# DataVideoPort.net
KiCad netlist of a schematic drawn in Altium Designer
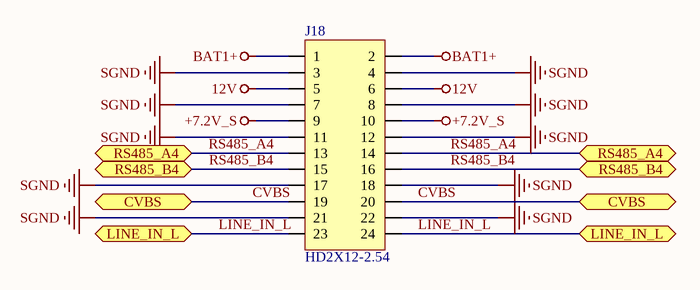
[diagram p0: DataVideoPort.SchDoc]

(export (version "E")
  (design (tool "Eeschema 10.0.6"))
  (components
    (comp (ref "J18")
      (value "HD2X12-2.54")
      (footprint "HD2X12-2.54")
      (libsource (lib "Connector Class") (part "HEADER2X12"))
    )
  )
  (nets
    (net (code "1") (name "+7.2V_S") (class "Default")
      (node (ref "J18") (pin "10") (pinfunction "10_10") (pintype "passive"))
      (node (ref "J18") (pin "9") (pinfunction "9_9") (pintype "passive"))
    )
    (net (code "2") (name "/CVBS") (class "Default")
      (node (ref "J18") (pin "19") (pinfunction "19_19") (pintype "passive"))
      (node (ref "J18") (pin "20") (pinfunction "20_20") (pintype "passive"))
    )
    (net (code "3") (name "/LINE_IN_L") (class "Default")
      (node (ref "J18") (pin "23") (pinfunction "23_23") (pintype "passive"))
      (node (ref "J18") (pin "24") (pinfunction "24_24") (pintype "passive"))
    )
    (net (code "4") (name "/RS485_A4") (class "Default")
      (node (ref "J18") (pin "13") (pinfunction "13_13") (pintype "passive"))
      (node (ref "J18") (pin "14") (pinfunction "14_14") (pintype "passive"))
    )
    (net (code "5") (name "/RS485_B4") (class "Default")
      (node (ref "J18") (pin "15") (pinfunction "15_15") (pintype "passive"))
      (node (ref "J18") (pin "16") (pinfunction "16_16") (pintype "passive"))
    )
    (net (code "6") (name "12V") (class "Default")
      (node (ref "J18") (pin "5") (pinfunction "5_5") (pintype "passive"))
      (node (ref "J18") (pin "6") (pinfunction "6_6") (pintype "passive"))
    )
    (net (code "7") (name "BAT1+") (class "Default")
      (node (ref "J18") (pin "1") (pinfunction "1_1") (pintype "passive"))
      (node (ref "J18") (pin "2") (pinfunction "2_2") (pintype "passive"))
    )
    (net (code "8") (name "SGND") (class "Default")
      (node (ref "J18") (pin "11") (pinfunction "11_11") (pintype "passive"))
      (node (ref "J18") (pin "12") (pinfunction "12_12") (pintype "passive"))
      (node (ref "J18") (pin "17") (pinfunction "17_17") (pintype "passive"))
      (node (ref "J18") (pin "18") (pinfunction "18_18") (pintype "passive"))
      (node (ref "J18") (pin "21") (pinfunction "21_21") (pintype "passive"))
      (node (ref "J18") (pin "22") (pinfunction "22_22") (pintype "passive"))
      (node (ref "J18") (pin "3") (pinfunction "3_3") (pintype "passive"))
      (node (ref "J18") (pin "4") (pinfunction "4_4") (pintype "passive"))
      (node (ref "J18") (pin "7") (pinfunction "7_7") (pintype "passive"))
      (node (ref "J18") (pin "8") (pinfunction "8_8") (pintype "passive"))
    )
  )
)
